# Schematic_Rev2.net
KiCad netlist of a schematic drawn in Altium Designer
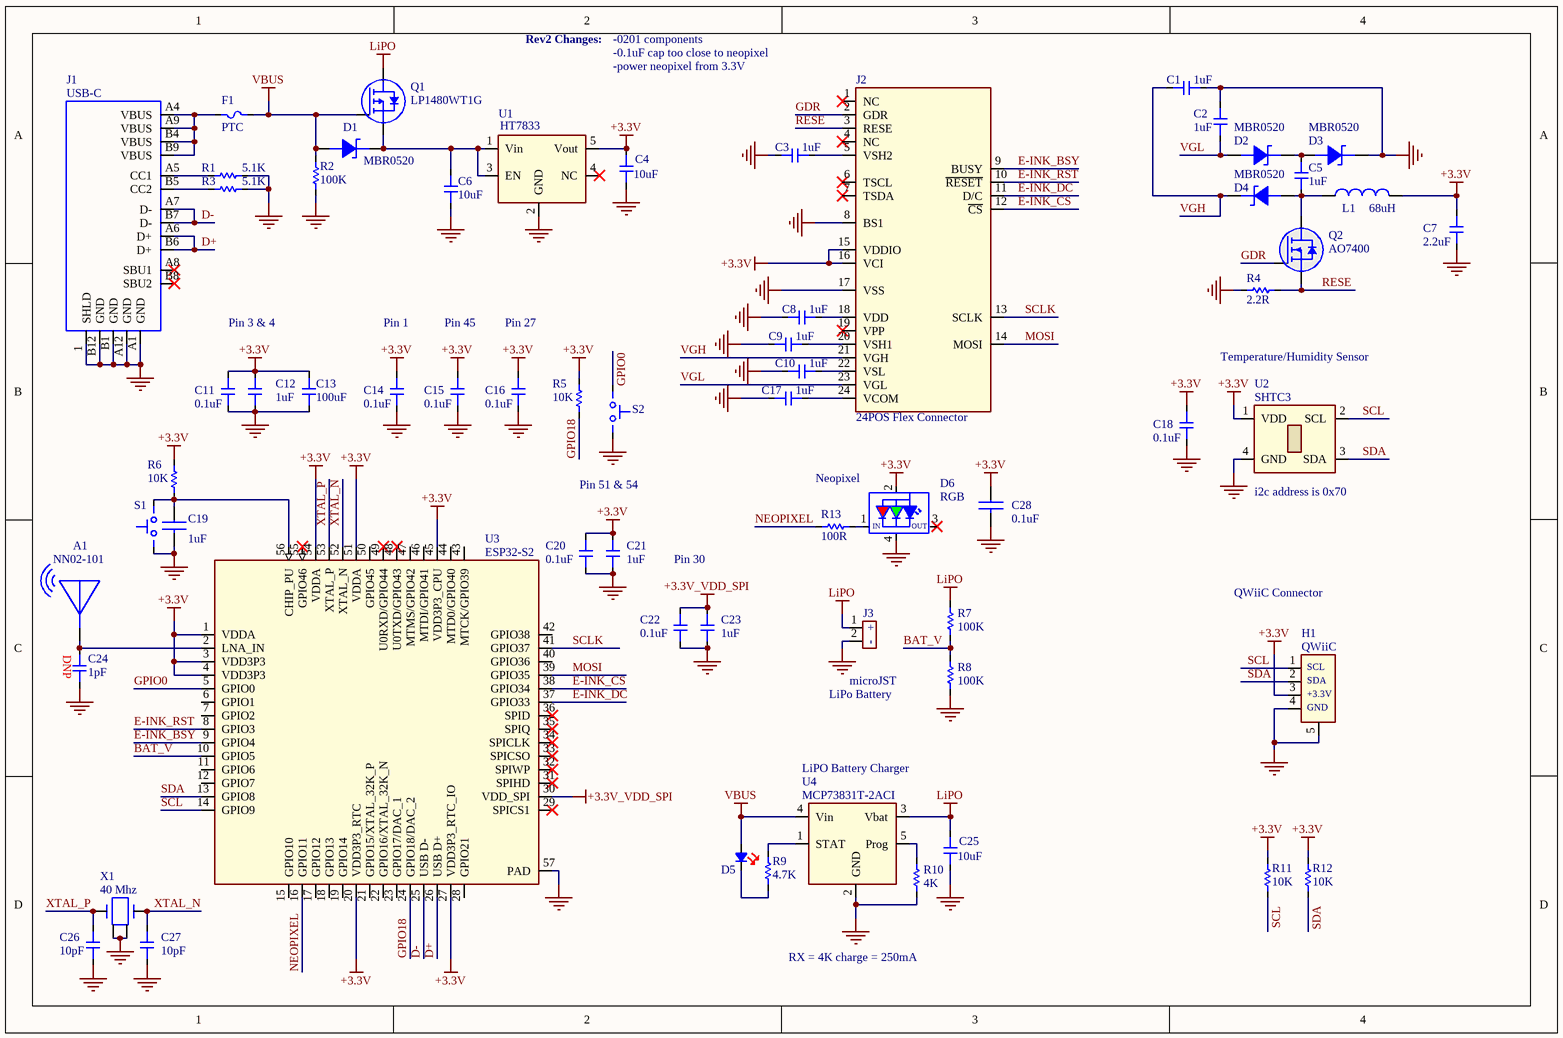
[diagram p0: Schematic_Rev2.SchDoc]

(export (version "E")
  (design (tool "Eeschema 10.0.6"))
  (components
    (comp (ref "A1")
      (value "NN02-101")
      (footprint "NN02-101")
      (description "Antenna Chip 2.4Gig")
      (fields (field (name "MANUFACTURER") "Ignion"))
      (libsource (lib "MAR") (part "NN02-101"))
    )
    (comp (ref "C1")
      (value "1uF")
      (footprint "CAPC1005X56N")
      (description "CAP 1uF 0402")
      (libsource (lib "MAR") (part "CAP_0402"))
    )
    (comp (ref "C2")
      (value "1uF")
      (footprint "CAPC1005X56N")
      (description "CAP 1uF 0402")
      (libsource (lib "MAR") (part "CAP_0402"))
    )
    (comp (ref "C3")
      (value "1uF")
      (footprint "CAPC1005X56N")
      (description "CAP 1uF 0402")
      (libsource (lib "MAR") (part "CAP_0402"))
    )
    (comp (ref "C4")
      (value "10uF")
      (footprint "CAPC2012X140N")
      (description "CAP 10uF 0805")
      (libsource (lib "MAR") (part "CAP_0805"))
    )
    (comp (ref "C5")
      (value "1uF")
      (footprint "CAPC1005X56N")
      (description "CAP 1uF 0402")
      (libsource (lib "MAR") (part "CAP_0402"))
    )
    (comp (ref "C6")
      (value "10uF")
      (footprint "CAPC2012X140N")
      (description "CAP 10uF 0805")
      (libsource (lib "MAR") (part "CAP_0805"))
    )
    (comp (ref "C7")
      (value "2.2uF")
      (footprint "CAPC1608X09L")
      (description "CAP 2.2uF 0603")
      (libsource (lib "MAR") (part "CAP_0402"))
    )
    (comp (ref "C8")
      (value "1uF")
      (footprint "CAPC1005X56N")
      (description "CAP 1uF 0402")
      (libsource (lib "MAR") (part "CAP_0402"))
    )
    (comp (ref "C9")
      (value "1uF")
      (footprint "CAPC1005X56N")
      (description "CAP 1uF 0402")
      (libsource (lib "MAR") (part "CAP_0402"))
    )
    (comp (ref "C10")
      (value "1uF")
      (footprint "CAPC1005X56N")
      (description "CAP 1uF 0402")
      (libsource (lib "MAR") (part "CAP_0402"))
    )
    (comp (ref "C11")
      (value "0.1uF")
      (footprint "CAPC1005X56N")
      (description "CAP 0.1uF 0402")
      (libsource (lib "MAR") (part "CAP_0402"))
    )
    (comp (ref "C12")
      (value "1uF")
      (footprint "CAPC1005X56N")
      (description "CAP 1uF 0402")
      (libsource (lib "MAR") (part "CAP_0402"))
    )
    (comp (ref "C13")
      (value "100uF")
      (footprint "CAPC3216X160N")
      (description "CAP 100uF 1206")
      (libsource (lib "MAR") (part "CAP_1206"))
    )
    (comp (ref "C14")
      (value "0.1uF")
      (footprint "CAPC1005X56N")
      (description "CAP 0.1uF 0402")
      (libsource (lib "MAR") (part "CAP_0402"))
    )
    (comp (ref "C15")
      (value "0.1uF")
      (footprint "CAPC1005X56N")
      (description "CAP 0.1uF 0402")
      (libsource (lib "MAR") (part "CAP_0402"))
    )
    (comp (ref "C16")
      (value "0.1uF")
      (footprint "CAPC1005X56N")
      (description "CAP 0.1uF 0402")
      (libsource (lib "MAR") (part "CAP_0402"))
    )
    (comp (ref "C17")
      (value "1uF")
      (footprint "CAPC1005X56N")
      (description "CAP 1uF 0402")
      (libsource (lib "MAR") (part "CAP_0402"))
    )
    (comp (ref "C18")
      (value "0.1uF")
      (footprint "CAPC1005X56N")
      (description "CAP 0.1uF 0402")
      (libsource (lib "MAR") (part "CAP_0402"))
    )
    (comp (ref "C19")
      (value "1uF")
      (footprint "CAPC1005X56N")
      (description "CAP 1uF 0402")
      (libsource (lib "") (part "CAP_0402_1"))
    )
    (comp (ref "C20")
      (value "0.1uF")
      (footprint "CAPC1005X56N")
      (description "CAP 0.1uF 0402")
      (libsource (lib "MAR") (part "CAP_0402"))
    )
    (comp (ref "C21")
      (value "1uF")
      (footprint "CAPC1005X56N")
      (description "CAP 1uF 0402")
      (libsource (lib "MAR") (part "CAP_0402"))
    )
    (comp (ref "C22")
      (value "0.1uF")
      (footprint "CAPC1005X56N")
      (description "CAP 0.1uF 0402")
      (libsource (lib "MAR") (part "CAP_0402"))
    )
    (comp (ref "C23")
      (value "1uF")
      (footprint "CAPC1005X56N")
      (description "CAP 0.1uF 0402")
      (libsource (lib "MAR") (part "CAP_0402"))
    )
    (comp (ref "C24")
      (value "1pF")
      (footprint "CAPC1005X56N")
      (description "CAP 1pF 0402")
      (libsource (lib "MAR") (part "CAP_0402"))
    )
    (comp (ref "C25")
      (value "10uF")
      (footprint "CAPC2012X140N")
      (description "CAP 10uF 0805")
      (libsource (lib "MAR") (part "CAP_0805"))
    )
    (comp (ref "C26")
      (value "10pF")
      (footprint "CAPC1005X56N")
      (description "CAP 10pF 0402")
      (libsource (lib "MAR") (part "CAP_0402"))
    )
    (comp (ref "C27")
      (value "10pF")
      (footprint "CAPC1005X56N")
      (description "CAP 10pF 0402")
      (libsource (lib "MAR") (part "CAP_0402"))
    )
    (comp (ref "C28")
      (value "0.1uF")
      (footprint "CAPC1005X56N")
      (description "CAP 0.1uF 0402")
      (libsource (lib "") (part "CAP_0402_1"))
    )
    (comp (ref "D1")
      (value "MBR0520")
      (footprint "SOD123")
      (description "DIODE SCHOTTKY 20V 500MA SOD-123")
      (fields (field (name "MANUFACTURER") "Micro") (field (name "PART_NUMBER") "C78746"))
      (libsource (lib "MAR") (part "MBR0520-TP"))
    )
    (comp (ref "D2")
      (value "MBR0520")
      (footprint "SOD123")
      (description "DIODE SCHOTTKY 20V 500MA SOD-123")
      (fields (field (name "MANUFACTURER") "Micro") (field (name "PART_NUMBER") "C78746"))
      (libsource (lib "MAR") (part "MBR0520-TP"))
    )
    (comp (ref "D3")
      (value "MBR0520")
      (footprint "SOD123")
      (description "DIODE SCHOTTKY 20V 500MA SOD-123")
      (fields (field (name "MANUFACTURER") "Micro") (field (name "PART_NUMBER") "C78746"))
      (libsource (lib "MAR") (part "MBR0520-TP"))
    )
    (comp (ref "D4")
      (value "MBR0520")
      (footprint "SOD123")
      (description "DIODE SCHOTTKY 20V 500MA SOD-123")
      (fields (field (name "MANUFACTURER") "Micro") (field (name "PART_NUMBER") "C78746"))
      (libsource (lib "MAR") (part "MBR0520-TP"))
    )
    (comp (ref "D5")
      (value "Red Led")
      (footprint "LED1005X40N-Red")
      (description "LED Red 0402")
      (fields (field (name "PART_NUMBER") "C364556") (field (name "MANUFACTURER") "Lite-On"))
      (libsource (lib "MAR") (part "LED_0402_SMALL_Red"))
    )
    (comp (ref "D6")
      (value "RGB")
      (footprint "SK6805-E-J")
      (description "LED,RGB,NEOPIXEL,SK6805-E-J 1515")
      (fields (field (name "PART_NUMBER") "4492") (field (name "MANUFACTURER") "Adafruit"))
      (libsource (lib "MAR") (part "SK6805-E-J-1515"))
    )
    (comp (ref "F1")
      (value "TLC-PSMD050")
      (footprint "RESC1608X06L (0603 FOOTPRINT)")
      (description "PTC FUSE 500mA hold, 1A trip")
      (fields (field (name "MANUFACTURER") "TLC") (field (name "PART_NUMBER") "C261942"))
      (libsource (lib "MAR") (part "PTC_FUSE"))
    )
    (comp (ref "H1")
      (value "QWiiC")
      (footprint "SM04B-SRSS-TB")
      (description "CONN HEADER 4POS .100 R/A QWIIC")
      (fields (field (name "MANUFACTURER") "JST") (field (name "PART_NUMBER") "PRT-14417"))
      (libsource (lib "MAR") (part "SM04B-SRSS-TB"))
    )
    (comp (ref "J1")
      (value "USB-C")
      (footprint "TYPE-C-31-M-12")
      (description "CONN RECPT USB-C")
      (fields (field (name "MANUFACTURER") "KHE") (field (name "PART_NUMBER") "C165948"))
      (libsource (lib "MAR") (part "USB-C"))
    )
    (comp (ref "J2")
      (value "24POS Flex Connector")
      (footprint "687124182122")
      (description "CONN FFC TOP/BOT 24POS 0.50MM R/A")
      (fields (field (name "MANUFACTURER") "Wurth") (field (name "PART_NUMBER") "687124182122"))
      (libsource (lib "MAR") (part "687124182122"))
    )
    (comp (ref "J3")
      (value "CON2")
      (footprint "JST_Micro_2PIN")
      (description "JST MIcro CONN 2POS")
      (libsource (lib "MAR") (part "JST_Micro_CONN_2PIN"))
    )
    (comp (ref "L1")
      (value "68uH")
      (footprint "INDUCTOR, 3mmX3mm")
      (description "INDUCTOR 68uH 20% 4mmx4mm")
      (fields (field (name "PART_NUMBER") "C135265") (field (name "MANUFACTURER") "SXN"))
      (libsource (lib "MAR") (part "68uH"))
    )
    (comp (ref "Q1")
      (value "LP1480WT1G")
      (footprint "SC-70")
      (description "MOSFET P-CH 20V 1.4A SC-70")
      (fields (field (name "MANUFACTURER") "LRC") (field (name "PART_NUMBER") "C172434"))
      (libsource (lib "MAR") (part "LP1480WT1G"))
    )
    (comp (ref "Q2")
      (value "AO7400")
      (footprint "SC-70")
      (description "MOSFET N-CH 20V 4A SC70-3")
      (fields (field (name "MANUFACTURER") "VBSemi Elec"))
      (libsource (lib "MAR") (part "AO7400"))
    )
    (comp (ref "R1")
      (value "5.1K")
      (footprint "RESC1005X40L (0402 FOOTPRINT)")
      (description "RES 5.1K 0402")
      (libsource (lib "MAR") (part "RES_0402"))
    )
    (comp (ref "R2")
      (value "100K")
      (footprint "RESC1005X40L (0402 FOOTPRINT)")
      (description "RES 100K 0402")
      (libsource (lib "MAR") (part "RES_0402"))
    )
    (comp (ref "R3")
      (value "5.1K")
      (footprint "RESC1005X40L (0402 FOOTPRINT)")
      (description "RES 5.1K 0402")
      (libsource (lib "MAR") (part "RES_0402"))
    )
    (comp (ref "R4")
      (value "2.2R")
      (footprint "RESC1005X40L (0402 FOOTPRINT)")
      (description "RES 2.2R 0402")
      (libsource (lib "MAR") (part "RES_0402"))
    )
    (comp (ref "R5")
      (value "10K")
      (footprint "RESC1005X40L (0402 FOOTPRINT)")
      (description "RES 10K 0402")
      (fields (field (name "LCSC_PART_NUMBER") "C258091") (field (name "MANUFACTURER") "Guangdong"))
      (libsource (lib "MAR") (part "RES_0402"))
    )
    (comp (ref "R6")
      (value "10K")
      (footprint "RESC1005X40L (0402 FOOTPRINT)")
      (description "RES 10K 0402")
      (fields (field (name "LCSC_PART_NUMBER") "C258091") (field (name "MANUFACTURER") "Guangdong"))
      (libsource (lib "MAR") (part "RES_0402"))
    )
    (comp (ref "R7")
      (value "100K")
      (footprint "RESC1005X40L (0402 FOOTPRINT)")
      (description "RES 100K 0402")
      (libsource (lib "MAR") (part "RES_0402"))
    )
    (comp (ref "R8")
      (value "100K")
      (footprint "RESC1005X40L (0402 FOOTPRINT)")
      (description "RES 100K 0402")
      (libsource (lib "MAR") (part "RES_0402"))
    )
    (comp (ref "R9")
      (value "4.7K")
      (footprint "RESC1005X40L (0402 FOOTPRINT)")
      (description "RES 4.7K 0402")
      (libsource (lib "MAR") (part "RES_0402"))
    )
    (comp (ref "R10")
      (value "4K")
      (footprint "RESC1005X40L (0402 FOOTPRINT)")
      (description "RES 4K 0402")
      (libsource (lib "MAR") (part "RES_0402"))
    )
    (comp (ref "R11")
      (value "10K")
      (footprint "RESC1005X40L (0402 FOOTPRINT)")
      (description "RES 10K 0402")
      (libsource (lib "MAR") (part "RES_0402"))
    )
    (comp (ref "R12")
      (value "10K")
      (footprint "RESC1005X40L (0402 FOOTPRINT)")
      (description "RES 10K 0402")
      (libsource (lib "MAR") (part "RES_0402"))
    )
    (comp (ref "R13")
      (value "100R")
      (footprint "RESC1005X40L (0402 FOOTPRINT)")
      (description "RES 100R 0402")
      (fields (field (name "MANUFACTURER") "Yageo") (field (name "PARTNUMBER") "C106232"))
      (libsource (lib "MAR") (part "RES_0603"))
    )
    (comp (ref "S1")
      (value "~")
      (footprint "TS-1088R-02526")
      (description "Tactile Micro Switch")
      (fields (field (name "PART_NUMBER") "C455281") (field (name "MANUFACTURER") "XUNPU"))
      (libsource (lib "MAR") (part "TS-1088R-02526"))
    )
    (comp (ref "S2")
      (value "~")
      (footprint "TS-1088R-02526")
      (description "Tactile Micro Switch")
      (fields (field (name "PART_NUMBER") "C455281") (field (name "MANUFACTURER") "XUNPU"))
      (libsource (lib "MAR") (part "TS-1088R-02526"))
    )
    (comp (ref "U1")
      (value "HT7833")
      (footprint "SOT95P280X144-5N")
      (description "IC LDO 3.3V 0.5A SOT23-5")
      (fields (field (name "MANUFACTURER") "Holtek") (field (name "PART_NUMBER") "C164106"))
      (libsource (lib "MAR") (part "HT7833"))
    )
    (comp (ref "U2")
      (value "SHTC3")
      (footprint "DFN-4 (2.0mm X 2.0mm)")
      (description "Humidity/Temperature Sensor")
      (fields (field (name "MANUFACTURER") "Sensirion") (field (name "PART_NUMBER") "SHTC3"))
      (libsource (lib "MAR") (part "SHTC3"))
    )
    (comp (ref "U3")
      (value "ESP32-S2")
      (footprint "QFN56_0.4mm pitch")
      (description "WIFI/Bluetooth, QFN-56 7x7")
      (fields (field (name "MANUFACTURER") "Espressif") (field (name "PART_NUMBER") "C529594"))
      (libsource (lib "MAR") (part "ESP32-S2"))
    )
    (comp (ref "U4")
      (value "MCP73831T-2ACI")
      (footprint "SOT95P280X144-5N")
      (description "Charger IC Lithium-Ion/Polymer SOT23-5")
      (fields (field (name "MANUFACTURER") "Microchip") (field (name "PART_NUMBER") "MCP73831T-2ACI/OT"))
      (libsource (lib "MAR") (part "MCP73831T-2ACI/OT"))
    )
    (comp (ref "X1")
      (value "40 Mhz")
      (footprint "OSC20X16")
      (description "CRYSTAL 40MHZ 10PF SMD")
      (fields (field (name "PART_NUMBER") "ECS-400-10-37B2-CKM") (field (name "MANUFACTURER") "ECS"))
      (libsource (lib "MAR") (part "40Mhz"))
    )
  )
  (nets
    (net (code "1") (name "+3.3V") (class "Default")
      (node (ref "C11") (pin "1") (pintype "passive"))
      (node (ref "C12") (pin "1") (pintype "passive"))
      (node (ref "C13") (pin "1") (pintype "passive"))
      (node (ref "C14") (pin "1") (pintype "passive"))
      (node (ref "C15") (pin "1") (pintype "passive"))
      (node (ref "C16") (pin "1") (pintype "passive"))
      (node (ref "C18") (pin "1") (pintype "passive"))
      (node (ref "C20") (pin "1") (pintype "passive"))
      (node (ref "C21") (pin "1") (pintype "passive"))
      (node (ref "C28") (pin "1") (pinfunction "1_1") (pintype "passive"))
      (node (ref "C4") (pin "1") (pintype "passive"))
      (node (ref "C7") (pin "1") (pintype "passive"))
      (node (ref "D6") (pin "2") (pinfunction "VDD_2") (pintype "passive"))
      (node (ref "H1") (pin "3") (pintype "passive"))
      (node (ref "J2") (pin "15") (pinfunction "VDDIO_15") (pintype "power_in"))
      (node (ref "J2") (pin "16") (pinfunction "VCI_16") (pintype "power_in"))
      (node (ref "L1") (pin "2") (pinfunction "2_2") (pintype "passive"))
      (node (ref "R11") (pin "2") (pintype "passive"))
      (node (ref "R12") (pin "2") (pintype "passive"))
      (node (ref "R5") (pin "1") (pintype "passive"))
      (node (ref "R6") (pin "1") (pintype "passive"))
      (node (ref "U1") (pin "5") (pinfunction "Vout_5") (pintype "passive"))
      (node (ref "U2") (pin "1") (pinfunction "VDD_1") (pintype "power_in"))
      (node (ref "U3") (pin "1") (pinfunction "VDDA_1") (pintype "power_in"))
      (node (ref "U3") (pin "20") (pinfunction "VDD3P3_RTC_20") (pintype "power_in"))
      (node (ref "U3") (pin "27") (pinfunction "VDD3P3_RTC_IO_27") (pintype "power_in"))
      (node (ref "U3") (pin "3") (pinfunction "VDD3P3_3") (pintype "power_in"))
      (node (ref "U3") (pin "4") (pinfunction "VDD3P3_4") (pintype "power_in"))
      (node (ref "U3") (pin "45") (pinfunction "VDD3P3_CPU_45") (pintype "power_in"))
      (node (ref "U3") (pin "51") (pinfunction "VDDA_51") (pintype "power_in"))
      (node (ref "U3") (pin "54") (pinfunction "VDDA_54") (pintype "power_in"))
    )
    (net (code "2") (name "+3.3V_VDD_SPI") (class "Default")
      (node (ref "C22") (pin "1") (pintype "passive"))
      (node (ref "C23") (pin "1") (pintype "passive"))
      (node (ref "U3") (pin "30") (pinfunction "VDD_SPI_30") (pintype "power_in"))
    )
    (net (code "3") (name "/BAT_V") (class "Default")
      (node (ref "R7") (pin "1") (pintype "passive"))
      (node (ref "R8") (pin "2") (pintype "passive"))
      (node (ref "U3") (pin "10") (pinfunction "GPIO5_10") (pintype "passive"))
    )
    (net (code "4") (name "/D+") (class "Default")
      (node (ref "J1") (pin "A6") (pinfunction "D+_A6") (pintype "power_in"))
      (node (ref "J1") (pin "B6") (pinfunction "D+_B6") (pintype "power_in"))
      (node (ref "U3") (pin "26") (pinfunction "USB_D+_26") (pintype "passive"))
    )
    (net (code "5") (name "/D-") (class "Default")
      (node (ref "J1") (pin "A7") (pinfunction "D-_A7") (pintype "power_in"))
      (node (ref "J1") (pin "B7") (pinfunction "D-_B7") (pintype "power_in"))
      (node (ref "U3") (pin "25") (pinfunction "USB_D-_25") (pintype "passive"))
    )
    (net (code "6") (name "/E-INK_BSY") (class "Default")
      (node (ref "J2") (pin "9") (pinfunction "BUSY_9") (pintype "passive"))
      (node (ref "U3") (pin "9") (pinfunction "GPIO4_9") (pintype "passive"))
    )
    (net (code "7") (name "/E-INK_CS") (class "Default")
      (node (ref "J2") (pin "12") (pinfunction "~{CS}_12") (pintype "passive"))
      (node (ref "U3") (pin "38") (pinfunction "GPIO34_38") (pintype "passive"))
    )
    (net (code "8") (name "/E-INK_DC") (class "Default")
      (node (ref "J2") (pin "11") (pinfunction "D/C_11") (pintype "passive"))
      (node (ref "U3") (pin "37") (pinfunction "GPIO33_37") (pintype "passive"))
    )
    (net (code "9") (name "/E-INK_RST") (class "Default")
      (node (ref "J2") (pin "10") (pinfunction "~{RESET}_10") (pintype "passive"))
      (node (ref "U3") (pin "8") (pinfunction "GPIO3_8") (pintype "passive"))
    )
    (net (code "10") (name "/GDR") (class "Default")
      (node (ref "J2") (pin "2") (pinfunction "GDR_2") (pintype "passive"))
      (node (ref "Q2") (pin "1") (pinfunction "G_1") (pintype "passive"))
    )
    (net (code "11") (name "/GPIO0") (class "Default")
      (node (ref "S2") (pin "1") (pinfunction "A_1") (pintype "passive"))
      (node (ref "U3") (pin "5") (pinfunction "GPIO0_5") (pintype "passive"))
    )
    (net (code "12") (name "/GPIO18") (class "Default")
      (node (ref "R5") (pin "2") (pintype "passive"))
      (node (ref "U3") (pin "24") (pinfunction "GPIO18/DAC_2_24") (pintype "passive"))
    )
    (net (code "13") (name "/MOSI") (class "Default")
      (node (ref "J2") (pin "14") (pinfunction "MOSI_14") (pintype "passive"))
      (node (ref "U3") (pin "39") (pinfunction "GPIO35_39") (pintype "passive"))
    )
    (net (code "14") (name "/NEOPIXEL") (class "Default")
      (node (ref "R13") (pin "2") (pintype "passive"))
      (node (ref "U3") (pin "16") (pinfunction "GPIO11_16") (pintype "passive"))
    )
    (net (code "15") (name "/RESE") (class "Default")
      (node (ref "J2") (pin "3") (pinfunction "RESE_3") (pintype "passive"))
      (node (ref "Q2") (pin "2") (pinfunction "S_2") (pintype "passive"))
      (node (ref "R4") (pin "1") (pintype "passive"))
    )
    (net (code "16") (name "/SCL") (class "Default")
      (node (ref "H1") (pin "1") (pintype "passive"))
      (node (ref "R11") (pin "1") (pintype "passive"))
      (node (ref "U2") (pin "2") (pinfunction "SCL_2") (pintype "passive"))
      (node (ref "U3") (pin "14") (pinfunction "GPIO9_14") (pintype "passive"))
    )
    (net (code "17") (name "/SCLK") (class "Default")
      (node (ref "J2") (pin "13") (pinfunction "SCLK_13") (pintype "passive"))
      (node (ref "U3") (pin "41") (pinfunction "GPIO37_41") (pintype "passive"))
    )
    (net (code "18") (name "/SDA") (class "Default")
      (node (ref "H1") (pin "2") (pintype "passive"))
      (node (ref "R12") (pin "1") (pintype "passive"))
      (node (ref "U2") (pin "3") (pinfunction "SDA_3") (pintype "passive"))
      (node (ref "U3") (pin "13") (pinfunction "GPIO8_13") (pintype "passive"))
    )
    (net (code "19") (name "/VGH") (class "Default")
      (node (ref "C1") (pin "1") (pintype "passive"))
      (node (ref "D4") (pin "1") (pinfunction "Cathode_1") (pintype "passive"))
      (node (ref "J2") (pin "21") (pinfunction "VGH_21") (pintype "passive"))
    )
    (net (code "20") (name "/VGL") (class "Default")
      (node (ref "C2") (pin "2") (pintype "passive"))
      (node (ref "D2") (pin "2") (pinfunction "Annode_2") (pintype "passive"))
      (node (ref "J2") (pin "23") (pinfunction "VGL_23") (pintype "passive"))
    )
    (net (code "21") (name "/XTAL_N") (class "Default")
      (node (ref "C27") (pin "1") (pintype "passive"))
      (node (ref "U3") (pin "52") (pinfunction "XTAL_N_52") (pintype "passive"))
      (node (ref "X1") (pin "3") (pinfunction "3_3") (pintype "passive"))
    )
    (net (code "22") (name "/XTAL_P") (class "Default")
      (node (ref "C26") (pin "1") (pintype "passive"))
      (node (ref "U3") (pin "53") (pinfunction "XTAL_P_53") (pintype "passive"))
      (node (ref "X1") (pin "1") (pinfunction "1_1") (pintype "passive"))
    )
    (net (code "23") (name "GND") (class "Default")
      (node (ref "C1") (pin "2") (pintype "passive"))
      (node (ref "C10") (pin "1") (pintype "passive"))
      (node (ref "C11") (pin "2") (pintype "passive"))
      (node (ref "C12") (pin "2") (pintype "passive"))
      (node (ref "C13") (pin "2") (pintype "passive"))
      (node (ref "C14") (pin "2") (pintype "passive"))
      (node (ref "C15") (pin "2") (pintype "passive"))
      (node (ref "C16") (pin "2") (pintype "passive"))
      (node (ref "C17") (pin "1") (pintype "passive"))
      (node (ref "C18") (pin "2") (pintype "passive"))
      (node (ref "C19") (pin "2") (pinfunction "2_2") (pintype "passive"))
      (node (ref "C2") (pin "1") (pintype "passive"))
      (node (ref "C20") (pin "2") (pintype "passive"))
      (node (ref "C21") (pin "2") (pintype "passive"))
      (node (ref "C22") (pin "2") (pintype "passive"))
      (node (ref "C23") (pin "2") (pintype "passive"))
      (node (ref "C24") (pin "2") (pintype "passive"))
      (node (ref "C25") (pin "2") (pintype "passive"))
      (node (ref "C26") (pin "2") (pintype "passive"))
      (node (ref "C27") (pin "2") (pintype "passive"))
      (node (ref "C28") (pin "2") (pinfunction "2_2") (pintype "passive"))
      (node (ref "C3") (pin "1") (pintype "passive"))
      (node (ref "C4") (pin "2") (pintype "passive"))
      (node (ref "C6") (pin "2") (pintype "passive"))
      (node (ref "C7") (pin "2") (pintype "passive"))
      (node (ref "C8") (pin "1") (pintype "passive"))
      (node (ref "C9") (pin "1") (pintype "passive"))
      (node (ref "D3") (pin "1") (pinfunction "Cathode_1") (pintype "passive"))
      (node (ref "D6") (pin "4") (pinfunction "GND_4") (pintype "passive"))
      (node (ref "H1") (pin "4") (pintype "passive"))
      (node (ref "H1") (pin "5") (pintype "passive"))
      (node (ref "J1") (pin "1") (pinfunction "SHLD_1") (pintype "power_in"))
      (node (ref "J1") (pin "A1") (pinfunction "GND_A1") (pintype "power_in"))
      (node (ref "J1") (pin "A12") (pinfunction "GND_A12") (pintype "power_in"))
      (node (ref "J1") (pin "B1") (pinfunction "GND_B1") (pintype "power_in"))
      (node (ref "J1") (pin "B12") (pinfunction "GND_B12") (pintype "passive"))
      (node (ref "J2") (pin "17") (pinfunction "VSS_17") (pintype "power_in"))
      (node (ref "J2") (pin "8") (pinfunction "BS1_8") (pintype "passive"))
      (node (ref "J3") (pin "2") (pintype "passive"))
      (node (ref "R1") (pin "1") (pintype "passive"))
      (node (ref "R10") (pin "1") (pintype "passive"))
      (node (ref "R2") (pin "2") (pintype "passive"))
      (node (ref "R3") (pin "1") (pintype "passive"))
      (node (ref "R4") (pin "2") (pintype "passive"))
      (node (ref "R8") (pin "1") (pintype "passive"))
      (node (ref "S1") (pin "2") (pinfunction "B_2") (pintype "passive"))
      (node (ref "S2") (pin "2") (pinfunction "B_2") (pintype "passive"))
      (node (ref "U1") (pin "2") (pinfunction "GND_2") (pintype "power_in"))
      (node (ref "U2") (pin "4") (pinfunction "GND_4") (pintype "power_in"))
      (node (ref "U3") (pin "57") (pinfunction "PAD_57") (pintype "power_in"))
      (node (ref "U4") (pin "2") (pinfunction "GND_2") (pintype "power_in"))
      (node (ref "X1") (pin "2") (pinfunction "2_2") (pintype "power_in"))
      (node (ref "X1") (pin "4") (pinfunction "4_4") (pintype "power_in"))
    )
    (net (code "24") (name "LiPO") (class "Default")
      (node (ref "C25") (pin "1") (pintype "passive"))
      (node (ref "J3") (pin "1") (pintype "passive"))
      (node (ref "Q1") (pin "3") (pinfunction "D_3") (pintype "passive"))
      (node (ref "R7") (pin "2") (pintype "passive"))
      (node (ref "U4") (pin "3") (pinfunction "Vbat_3") (pintype "passive"))
    )
    (net (code "25") (name "Net-(D1-Cathode)") (class "Default")
      (node (ref "C6") (pin "1") (pintype "passive"))
      (node (ref "D1") (pin "1") (pinfunction "Cathode_1") (pintype "passive"))
      (node (ref "Q1") (pin "2") (pinfunction "S_2") (pintype "passive"))
      (node (ref "U1") (pin "1") (pinfunction "Vin_1") (pintype "passive"))
      (node (ref "U1") (pin "3") (pinfunction "EN_3") (pintype "passive"))
    )
    (net (code "26") (name "Net-(D2-Cathode)") (class "Default")
      (node (ref "C5") (pin "1") (pintype "passive"))
      (node (ref "D2") (pin "1") (pinfunction "Cathode_1") (pintype "passive"))
      (node (ref "D3") (pin "2") (pinfunction "Annode_2") (pintype "passive"))
    )
    (net (code "27") (name "Net-(D4-Annode)") (class "Default")
      (node (ref "C5") (pin "2") (pintype "passive"))
      (node (ref "D4") (pin "2") (pinfunction "Annode_2") (pintype "passive"))
      (node (ref "L1") (pin "1") (pinfunction "1_1") (pintype "passive"))
      (node (ref "Q2") (pin "3") (pinfunction "D_3") (pintype "passive"))
    )
    (net (code "28") (name "Net-(D5-Pad1)") (class "Default")
      (node (ref "D5") (pin "1") (pintype "passive"))
      (node (ref "R9") (pin "1") (pintype "passive"))
    )
    (net (code "29") (name "Net-(D6-DIN)") (class "Default")
      (node (ref "D6") (pin "1") (pinfunction "DIN_1") (pintype "passive"))
      (node (ref "R13") (pin "1") (pintype "passive"))
    )
    (net (code "30") (name "Net-(F1-Pad2)") (class "Default")
      (node (ref "F1") (pin "2") (pintype "passive"))
      (node (ref "J1") (pin "A4") (pinfunction "VBUS_A4") (pintype "passive"))
      (node (ref "J1") (pin "A9") (pinfunction "VBUS_A9") (pintype "power_in"))
      (node (ref "J1") (pin "B4") (pinfunction "VBUS_B4") (pintype "power_in"))
      (node (ref "J1") (pin "B9") (pinfunction "VBUS_B9") (pintype "passive"))
    )
    (net (code "31") (name "Net-(J1-CC1)") (class "Default")
      (node (ref "J1") (pin "A5") (pinfunction "CC1_A5") (pintype "power_in"))
      (node (ref "R1") (pin "2") (pintype "passive"))
    )
    (net (code "32") (name "Net-(J1-CC2)") (class "Default")
      (node (ref "J1") (pin "B5") (pinfunction "CC2_B5") (pintype "power_in"))
      (node (ref "R3") (pin "2") (pintype "passive"))
    )
    (net (code "33") (name "Net-(J2-VCOM)") (class "Default")
      (node (ref "C17") (pin "2") (pintype "passive"))
      (node (ref "J2") (pin "24") (pinfunction "VCOM_24") (pintype "passive"))
    )
    (net (code "34") (name "Net-(J2-VDD)") (class "Default")
      (node (ref "C8") (pin "2") (pintype "passive"))
      (node (ref "J2") (pin "18") (pinfunction "VDD_18") (pintype "power_in"))
    )
    (net (code "35") (name "Net-(J2-VSH1)") (class "Default")
      (node (ref "C9") (pin "2") (pintype "passive"))
      (node (ref "J2") (pin "20") (pinfunction "VSH1_20") (pintype "passive"))
    )
    (net (code "36") (name "Net-(J2-VSH2)") (class "Default")
      (node (ref "C3") (pin "2") (pintype "passive"))
      (node (ref "J2") (pin "5") (pinfunction "VSH2_5") (pintype "passive"))
    )
    (net (code "37") (name "Net-(J2-VSL)") (class "Default")
      (node (ref "C10") (pin "2") (pintype "passive"))
      (node (ref "J2") (pin "22") (pinfunction "VSL_22") (pintype "passive"))
    )
    (net (code "38") (name "Net-(S1-A)") (class "Default")
      (node (ref "C19") (pin "1") (pinfunction "1_1") (pintype "passive"))
      (node (ref "R6") (pin "2") (pintype "passive"))
      (node (ref "S1") (pin "1") (pinfunction "A_1") (pintype "passive"))
      (node (ref "U3") (pin "56") (pinfunction "CHIP_PU_56") (pintype "input"))
    )
    (net (code "39") (name "Net-(U3-LNA_IN)") (class "Default")
      (node (ref "A1") (pin "1") (pintype "passive"))
      (node (ref "C24") (pin "1") (pintype "passive"))
      (node (ref "U3") (pin "2") (pinfunction "LNA_IN_2") (pintype "passive"))
    )
    (net (code "40") (name "Net-(U4-Prog)") (class "Default")
      (node (ref "R10") (pin "2") (pintype "passive"))
      (node (ref "U4") (pin "5") (pinfunction "Prog_5") (pintype "passive"))
    )
    (net (code "41") (name "Net-(U4-STAT)") (class "Default")
      (node (ref "R9") (pin "2") (pintype "passive"))
      (node (ref "U4") (pin "1") (pinfunction "STAT_1") (pintype "passive"))
    )
    (net (code "42") (name "VBUS") (class "Default")
      (node (ref "D1") (pin "2") (pinfunction "Annode_2") (pintype "passive"))
      (node (ref "D5") (pin "2") (pintype "passive"))
      (node (ref "F1") (pin "1") (pintype "passive"))
      (node (ref "Q1") (pin "1") (pinfunction "G_1") (pintype "passive"))
      (node (ref "R2") (pin "1") (pintype "passive"))
      (node (ref "U4") (pin "4") (pinfunction "Vin_4") (pintype "passive"))
    )
    (net (code "43") (name "unconnected-(D6-DOUT-Pad3)") (class "Default")
      (node (ref "D6") (pin "3") (pinfunction "DOUT_3") (pintype "passive+no_connect"))
    )
    (net (code "44") (name "unconnected-(J1-SBU1-PadA8)") (class "Default")
      (node (ref "J1") (pin "A8") (pinfunction "SBU1_A8") (pintype "power_in+no_connect"))
    )
    (net (code "45") (name "unconnected-(J1-SBU2-PadB8)") (class "Default")
      (node (ref "J1") (pin "B8") (pinfunction "SBU2_B8") (pintype "power_in+no_connect"))
    )
    (net (code "46") (name "unconnected-(J2-NC-Pad1)") (class "Default")
      (node (ref "J2") (pin "1") (pinfunction "NC_1") (pintype "passive+no_connect"))
    )
    (net (code "47") (name "unconnected-(J2-NC-Pad4)") (class "Default")
      (node (ref "J2") (pin "4") (pinfunction "NC_4") (pintype "passive+no_connect"))
    )
    (net (code "48") (name "unconnected-(J2-TSCL-Pad6)") (class "Default")
      (node (ref "J2") (pin "6") (pinfunction "TSCL_6") (pintype "passive+no_connect"))
    )
    (net (code "49") (name "unconnected-(J2-TSDA-Pad7)") (class "Default")
      (node (ref "J2") (pin "7") (pinfunction "TSDA_7") (pintype "passive+no_connect"))
    )
    (net (code "50") (name "unconnected-(J2-VPP-Pad19)") (class "Default")
      (node (ref "J2") (pin "19") (pinfunction "VPP_19") (pintype "passive+no_connect"))
    )
    (net (code "51") (name "unconnected-(U1-NC-Pad4)") (class "Default")
      (node (ref "U1") (pin "4") (pinfunction "NC_4") (pintype "passive+no_connect"))
    )
    (net (code "52") (name "unconnected-(U3-GPIO1-Pad6)") (class "Default")
      (node (ref "U3") (pin "6") (pinfunction "GPIO1_6") (pintype "passive"))
    )
    (net (code "53") (name "unconnected-(U3-GPIO2-Pad7)") (class "Default")
      (node (ref "U3") (pin "7") (pinfunction "GPIO2_7") (pintype "passive"))
    )
    (net (code "54") (name "unconnected-(U3-GPIO6-Pad11)") (class "Default")
      (node (ref "U3") (pin "11") (pinfunction "GPIO6_11") (pintype "passive"))
    )
    (net (code "55") (name "unconnected-(U3-GPIO7-Pad12)") (class "Default")
      (node (ref "U3") (pin "12") (pinfunction "GPIO7_12") (pintype "passive"))
    )
    (net (code "56") (name "unconnected-(U3-GPIO10-Pad15)") (class "Default")
      (node (ref "U3") (pin "15") (pinfunction "GPIO10_15") (pintype "passive"))
    )
    (net (code "57") (name "unconnected-(U3-GPIO12-Pad17)") (class "Default")
      (node (ref "U3") (pin "17") (pinfunction "GPIO12_17") (pintype "passive"))
    )
    (net (code "58") (name "unconnected-(U3-GPIO13-Pad18)") (class "Default")
      (node (ref "U3") (pin "18") (pinfunction "GPIO13_18") (pintype "passive"))
    )
    (net (code "59") (name "unconnected-(U3-GPIO14-Pad19)") (class "Default")
      (node (ref "U3") (pin "19") (pinfunction "GPIO14_19") (pintype "passive"))
    )
    (net (code "60") (name "unconnected-(U3-GPIO15{slash}XTAL_32K_P-Pad21)") (class "Default")
      (node (ref "U3") (pin "21") (pinfunction "GPIO15/XTAL_32K_P_21") (pintype "passive"))
    )
    (net (code "61") (name "unconnected-(U3-GPIO16{slash}XTAL_32K_N-Pad22)") (class "Default")
      (node (ref "U3") (pin "22") (pinfunction "GPIO16/XTAL_32K_N_22") (pintype "passive"))
    )
    (net (code "62") (name "unconnected-(U3-GPIO17{slash}DAC_1-Pad23)") (class "Default")
      (node (ref "U3") (pin "23") (pinfunction "GPIO17/DAC_1_23") (pintype "passive"))
    )
    (net (code "63") (name "unconnected-(U3-GPIO21-Pad28)") (class "Default")
      (node (ref "U3") (pin "28") (pinfunction "GPIO21_28") (pintype "passive"))
    )
    (net (code "64") (name "unconnected-(U3-GPIO36-Pad40)") (class "Default")
      (node (ref "U3") (pin "40") (pinfunction "GPIO36_40") (pintype "passive"))
    )
    (net (code "65") (name "unconnected-(U3-GPIO38-Pad42)") (class "Default")
      (node (ref "U3") (pin "42") (pinfunction "GPIO38_42") (pintype "passive"))
    )
    (net (code "66") (name "unconnected-(U3-GPIO45-Pad50)") (class "Default")
      (node (ref "U3") (pin "50") (pinfunction "GPIO45_50") (pintype "passive"))
    )
    (net (code "67") (name "unconnected-(U3-GPIO46-Pad55)") (class "Default")
      (node (ref "U3") (pin "55") (pinfunction "GPIO46_55") (pintype "input+no_connect"))
    )
    (net (code "68") (name "unconnected-(U3-MTCK{slash}GPIO39-Pad43)") (class "Default")
      (node (ref "U3") (pin "43") (pinfunction "MTCK/GPIO39_43") (pintype "passive"))
    )
    (net (code "69") (name "unconnected-(U3-MTD0{slash}GPIO40-Pad44)") (class "Default")
      (node (ref "U3") (pin "44") (pinfunction "MTD0/GPIO40_44") (pintype "passive"))
    )
    (net (code "70") (name "unconnected-(U3-MTDI{slash}GPIO41-Pad46)") (class "Default")
      (node (ref "U3") (pin "46") (pinfunction "MTDI/GPIO41_46") (pintype "passive"))
    )
    (net (code "71") (name "unconnected-(U3-MTMS{slash}GPIO42-Pad47)") (class "Default")
      (node (ref "U3") (pin "47") (pinfunction "MTMS/GPIO42_47") (pintype "passive"))
    )
    (net (code "72") (name "unconnected-(U3-SPICLK-Pad34)") (class "Default")
      (node (ref "U3") (pin "34") (pinfunction "SPICLK_34") (pintype "passive+no_connect"))
    )
    (net (code "73") (name "unconnected-(U3-SPICS1-Pad29)") (class "Default")
      (node (ref "U3") (pin "29") (pinfunction "SPICS1_29") (pintype "passive+no_connect"))
    )
    (net (code "74") (name "unconnected-(U3-SPICSO-Pad33)") (class "Default")
      (node (ref "U3") (pin "33") (pinfunction "SPICSO_33") (pintype "passive+no_connect"))
    )
    (net (code "75") (name "unconnected-(U3-SPID-Pad36)") (class "Default")
      (node (ref "U3") (pin "36") (pinfunction "SPID_36") (pintype "passive+no_connect"))
    )
    (net (code "76") (name "unconnected-(U3-SPIHD-Pad31)") (class "Default")
      (node (ref "U3") (pin "31") (pinfunction "SPIHD_31") (pintype "passive+no_connect"))
    )
    (net (code "77") (name "unconnected-(U3-SPIQ-Pad35)") (class "Default")
      (node (ref "U3") (pin "35") (pinfunction "SPIQ_35") (pintype "passive+no_connect"))
    )
    (net (code "78") (name "unconnected-(U3-SPIWP-Pad32)") (class "Default")
      (node (ref "U3") (pin "32") (pinfunction "SPIWP_32") (pintype "passive+no_connect"))
    )
    (net (code "79") (name "unconnected-(U3-U0RXD{slash}GPIO44-Pad49)") (class "Default")
      (node (ref "U3") (pin "49") (pinfunction "U0RXD/GPIO44_49") (pintype "passive+no_connect"))
    )
    (net (code "80") (name "unconnected-(U3-U0TXD{slash}GPIO43-Pad48)") (class "Default")
      (node (ref "U3") (pin "48") (pinfunction "U0TXD/GPIO43_48") (pintype "passive+no_connect"))
    )
  )
)
